# schemat_polaczen3.net
KiCad netlist of a schematic drawn in EAGLE
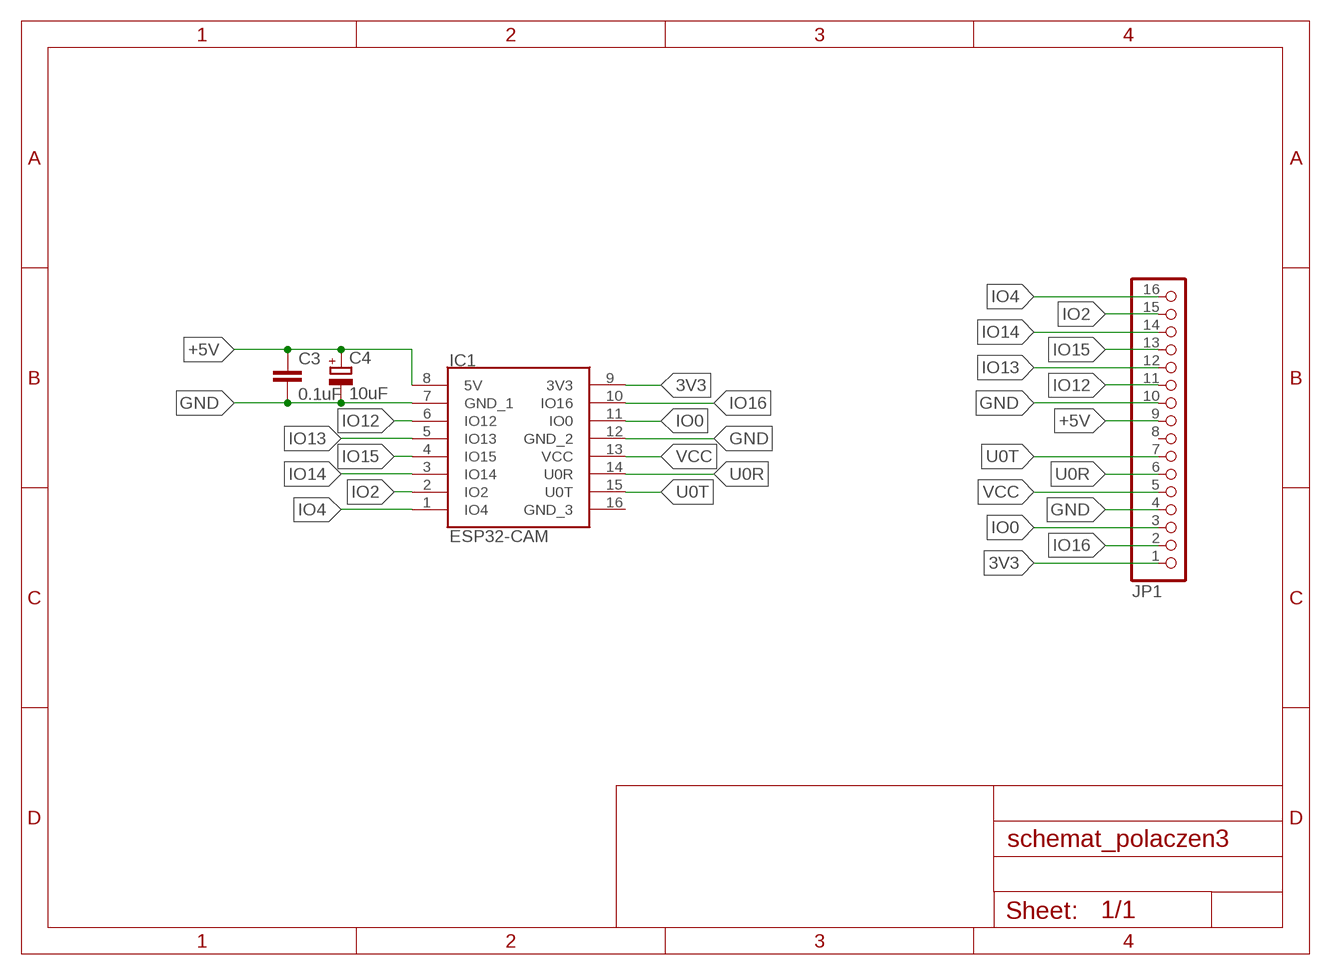
[diagram p0: schematic, sheet 1]

(export (version "E")
  (design (tool "Eeschema 10.0.6"))
  (components
    (comp (ref "C3")
      (value "0.1uF")
      (footprint "eagle-import:C025-024X044")
      (libsource (lib "eagle-import") (part "C-EU025-024X044"))
    )
    (comp (ref "C4")
      (value "10uF")
      (footprint "eagle-import:E2,5-6E")
      (libsource (lib "eagle-import") (part "CPOL-EUE2,5-6E"))
    )
    (comp (ref "IC1")
      (value "ESP32-CAM")
      (footprint "eagle-import:ESP32CAM")
      (libsource (lib "eagle-import") (part "ESP32-CAM"))
    )
    (comp (ref "JP1")
      (value "PINHD-1X16/90")
      (footprint "eagle-import:1X16_90")
      (libsource (lib "eagle-import") (part "PINHD-1X16/90"))
    )
  )
  (nets
    (net (code "1") (name "+5V") (class "Default")
      (node (ref "C3") (pin "1") (pinfunction "1_1") (pintype "passive"))
      (node (ref "C4") (pin "+") (pinfunction "+_+") (pintype "passive"))
      (node (ref "IC1") (pin "8") (pinfunction "5V_8") (pintype "bidirectional"))
      (node (ref "JP1") (pin "9") (pinfunction "9_9") (pintype "passive"))
    )
    (net (code "2") (name "3V3") (class "Default")
      (node (ref "IC1") (pin "9") (pinfunction "3V3_9") (pintype "bidirectional"))
      (node (ref "JP1") (pin "1") (pinfunction "1_1") (pintype "passive"))
    )
    (net (code "3") (name "GND") (class "Default")
      (node (ref "C3") (pin "2") (pinfunction "2_2") (pintype "passive"))
      (node (ref "C4") (pin "-") (pinfunction "-_-") (pintype "passive"))
      (node (ref "IC1") (pin "12") (pinfunction "GND_2_12") (pintype "bidirectional"))
      (node (ref "IC1") (pin "7") (pinfunction "GND_1_7") (pintype "bidirectional"))
      (node (ref "JP1") (pin "10") (pinfunction "10_10") (pintype "passive"))
      (node (ref "JP1") (pin "4") (pinfunction "4_4") (pintype "passive"))
    )
    (net (code "4") (name "IO0") (class "Default")
      (node (ref "IC1") (pin "11") (pinfunction "IO0_11") (pintype "bidirectional"))
      (node (ref "JP1") (pin "3") (pinfunction "3_3") (pintype "passive"))
    )
    (net (code "5") (name "IO2") (class "Default")
      (node (ref "IC1") (pin "2") (pinfunction "IO2_2") (pintype "bidirectional"))
      (node (ref "JP1") (pin "15") (pinfunction "15_15") (pintype "passive"))
    )
    (net (code "6") (name "IO4") (class "Default")
      (node (ref "IC1") (pin "1") (pinfunction "IO4_1") (pintype "bidirectional"))
      (node (ref "JP1") (pin "16") (pinfunction "16_16") (pintype "passive"))
    )
    (net (code "7") (name "IO12") (class "Default")
      (node (ref "IC1") (pin "6") (pinfunction "IO12_6") (pintype "bidirectional"))
      (node (ref "JP1") (pin "11") (pinfunction "11_11") (pintype "passive"))
    )
    (net (code "8") (name "IO13") (class "Default")
      (node (ref "IC1") (pin "5") (pinfunction "IO13_5") (pintype "bidirectional"))
      (node (ref "JP1") (pin "12") (pinfunction "12_12") (pintype "passive"))
    )
    (net (code "9") (name "IO14") (class "Default")
      (node (ref "IC1") (pin "3") (pinfunction "IO14_3") (pintype "bidirectional"))
      (node (ref "JP1") (pin "14") (pinfunction "14_14") (pintype "passive"))
    )
    (net (code "10") (name "IO15") (class "Default")
      (node (ref "IC1") (pin "4") (pinfunction "IO15_4") (pintype "bidirectional"))
      (node (ref "JP1") (pin "13") (pinfunction "13_13") (pintype "passive"))
    )
    (net (code "11") (name "IO16") (class "Default")
      (node (ref "IC1") (pin "10") (pinfunction "IO16_10") (pintype "bidirectional"))
      (node (ref "JP1") (pin "2") (pinfunction "2_2") (pintype "passive"))
    )
    (net (code "12") (name "U0R") (class "Default")
      (node (ref "IC1") (pin "14") (pinfunction "U0R_14") (pintype "bidirectional"))
      (node (ref "JP1") (pin "6") (pinfunction "6_6") (pintype "passive"))
    )
    (net (code "13") (name "U0T") (class "Default")
      (node (ref "IC1") (pin "15") (pinfunction "U0T_15") (pintype "bidirectional"))
      (node (ref "JP1") (pin "7") (pinfunction "7_7") (pintype "passive"))
    )
    (net (code "14") (name "VCC") (class "Default")
      (node (ref "IC1") (pin "13") (pinfunction "VCC_13") (pintype "bidirectional"))
      (node (ref "JP1") (pin "5") (pinfunction "5_5") (pintype "passive"))
    )
    (net (code "15") (name "unconnected-(IC1-GND_3-Pad16)") (class "Default")
      (node (ref "IC1") (pin "16") (pinfunction "GND_3_16") (pintype "bidirectional"))
    )
    (net (code "16") (name "unconnected-(JP1-Pad8)") (class "Default")
      (node (ref "JP1") (pin "8") (pinfunction "8_8") (pintype "passive"))
    )
  )
)
